# optocoupler_3.net
KiCad netlist of a schematic drawn in EAGLE
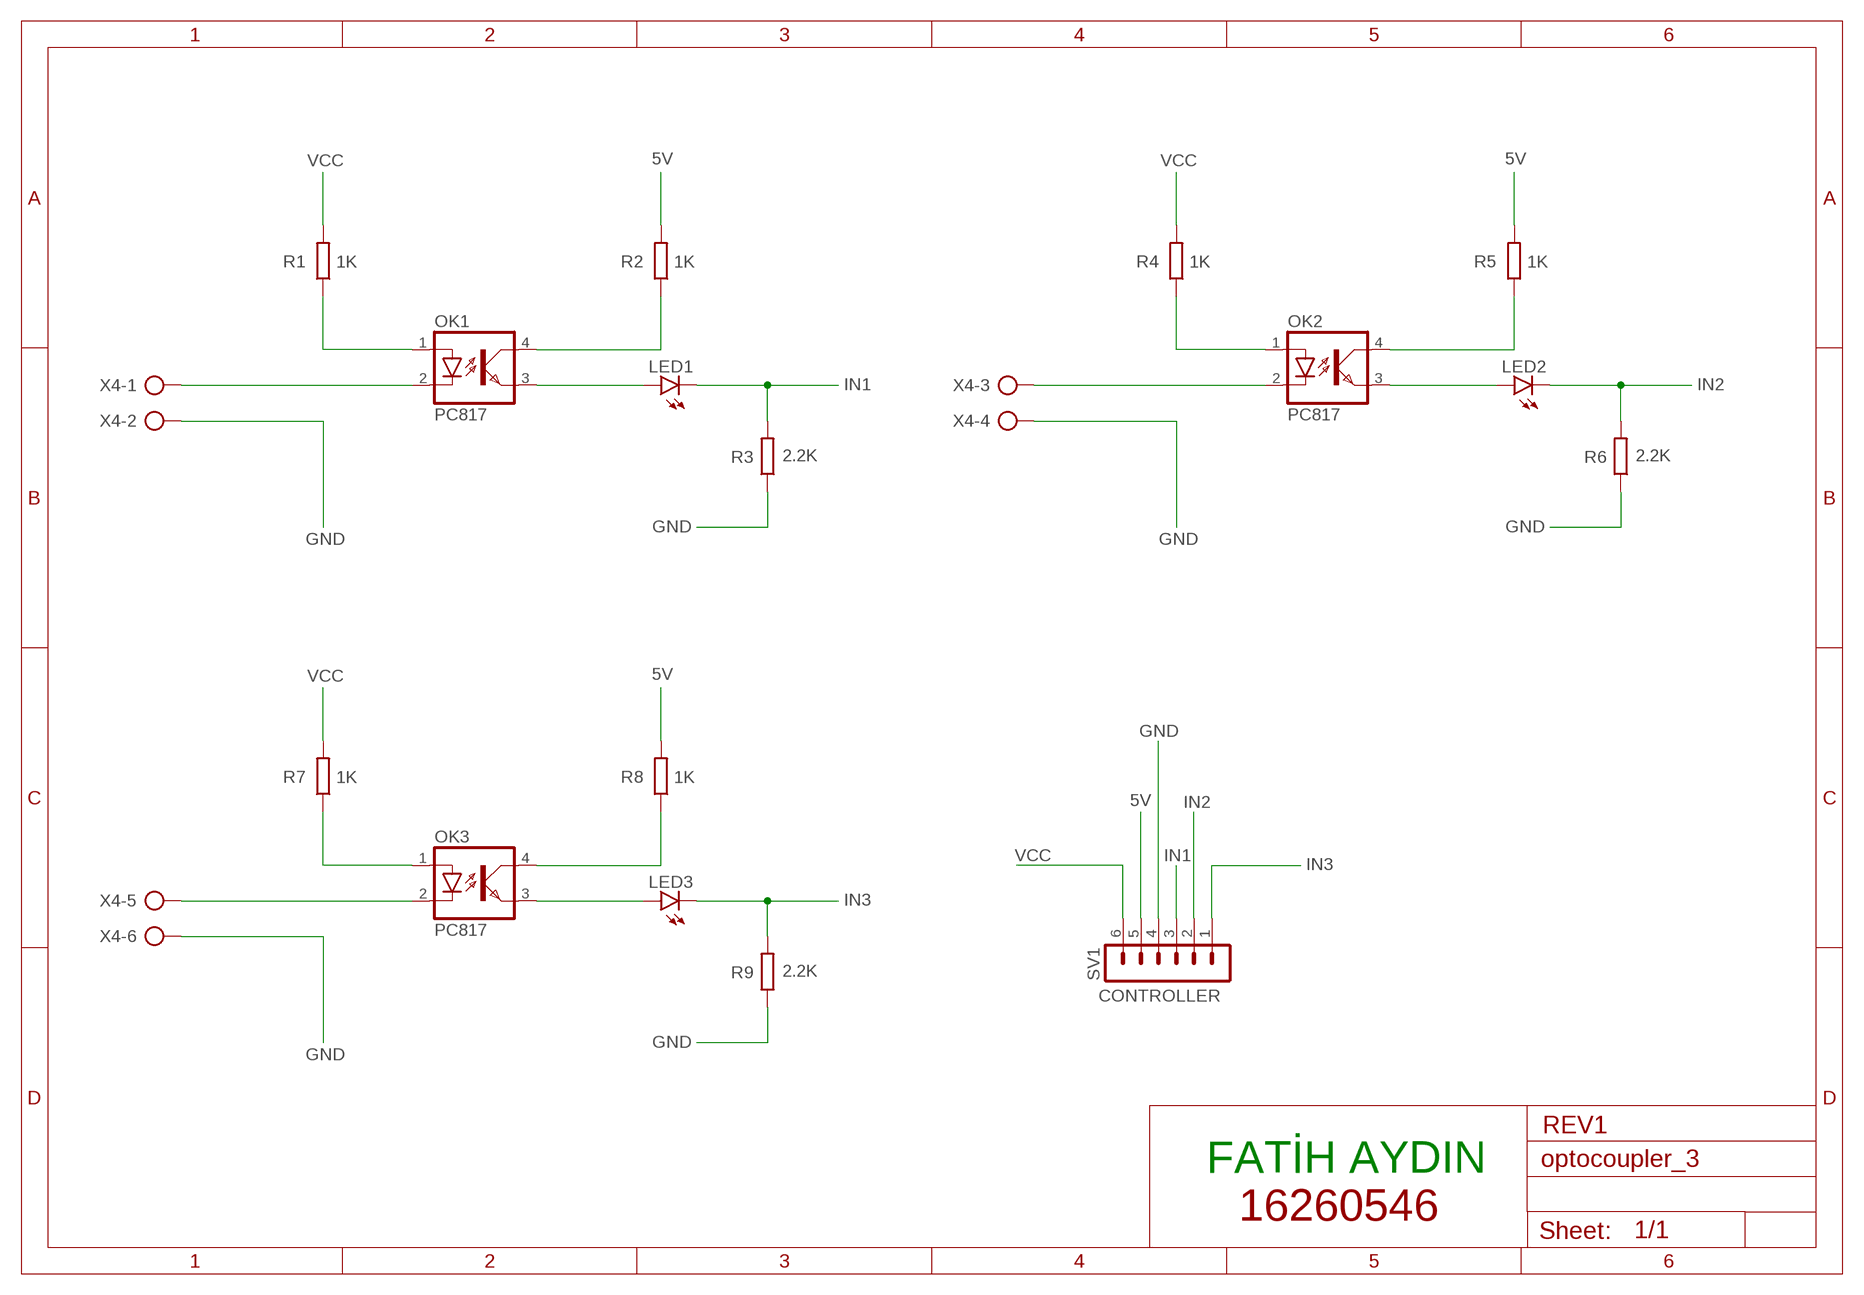
[diagram p0: schematic, sheet 1]

(export (version "E")
  (design (tool "Eeschema 10.0.6"))
  (components
    (comp (ref "LED1")
      (value "LED5MM")
      (footprint "eagle-import:LED5MM")
      (libsource (lib "eagle-import") (part "LED5MM"))
    )
    (comp (ref "LED2")
      (value "LED5MM")
      (footprint "eagle-import:LED5MM")
      (libsource (lib "eagle-import") (part "LED5MM"))
    )
    (comp (ref "LED3")
      (value "LED5MM")
      (footprint "eagle-import:LED5MM")
      (libsource (lib "eagle-import") (part "LED5MM"))
    )
    (comp (ref "OK1")
      (value "PC817")
      (footprint "eagle-import:DIL04")
      (fields (field (name "MPN") "PC817X4J000F"))
      (libsource (lib "eagle-import") (part "PC817"))
    )
    (comp (ref "OK2")
      (value "PC817")
      (footprint "eagle-import:DIL04")
      (fields (field (name "MPN") "PC817X4J000F"))
      (libsource (lib "eagle-import") (part "PC817"))
    )
    (comp (ref "OK3")
      (value "PC817")
      (footprint "eagle-import:DIL04")
      (fields (field (name "MPN") "PC817X4J000F"))
      (libsource (lib "eagle-import") (part "PC817"))
    )
    (comp (ref "R1")
      (value "1K")
      (footprint "eagle-import:0204_7")
      (libsource (lib "eagle-import") (part "R-EU_0204/7"))
    )
    (comp (ref "R2")
      (value "1K")
      (footprint "eagle-import:0204_7")
      (libsource (lib "eagle-import") (part "R-EU_0204/7"))
    )
    (comp (ref "R3")
      (value "2.2K")
      (footprint "eagle-import:0204_7")
      (libsource (lib "eagle-import") (part "R-EU_0204/7"))
    )
    (comp (ref "R4")
      (value "1K")
      (footprint "eagle-import:0204_7")
      (libsource (lib "eagle-import") (part "R-EU_0204/7"))
    )
    (comp (ref "R5")
      (value "1K")
      (footprint "eagle-import:0204_7")
      (libsource (lib "eagle-import") (part "R-EU_0204/7"))
    )
    (comp (ref "R6")
      (value "2.2K")
      (footprint "eagle-import:0204_7")
      (libsource (lib "eagle-import") (part "R-EU_0204/7"))
    )
    (comp (ref "R7")
      (value "1K")
      (footprint "eagle-import:0204_7")
      (libsource (lib "eagle-import") (part "R-EU_0204/7"))
    )
    (comp (ref "R8")
      (value "1K")
      (footprint "eagle-import:0204_7")
      (libsource (lib "eagle-import") (part "R-EU_0204/7"))
    )
    (comp (ref "R9")
      (value "2.2K")
      (footprint "eagle-import:0204_7")
      (libsource (lib "eagle-import") (part "R-EU_0204/7"))
    )
    (comp (ref "SV1")
      (value "CONTROLLER")
      (footprint "eagle-import:MA06-1")
      (libsource (lib "eagle-import") (part "MA06-1"))
    )
    (comp (ref "X4")
      (value "AK300/6")
      (footprint "eagle-import:AK300_6")
      (libsource (lib "eagle-import") (part "AK300/6"))
    )
  )
  (nets
    (net (code "1") (name "/5V") (class "Default")
      (node (ref "R2") (pin "2") (pinfunction "2_2") (pintype "passive"))
      (node (ref "R5") (pin "2") (pinfunction "2_2") (pintype "passive"))
      (node (ref "R8") (pin "2") (pinfunction "2_2") (pintype "passive"))
      (node (ref "SV1") (pin "5") (pinfunction "5_5") (pintype "passive"))
    )
    (net (code "2") (name "/GND") (class "Default")
      (node (ref "R3") (pin "1") (pinfunction "1_1") (pintype "passive"))
      (node (ref "R6") (pin "1") (pinfunction "1_1") (pintype "passive"))
      (node (ref "R9") (pin "1") (pinfunction "1_1") (pintype "passive"))
      (node (ref "SV1") (pin "4") (pinfunction "4_4") (pintype "passive"))
      (node (ref "X4") (pin "2") (pinfunction "KL_2") (pintype "passive"))
      (node (ref "X4") (pin "4") (pinfunction "KL_4") (pintype "passive"))
      (node (ref "X4") (pin "6") (pinfunction "KL_6") (pintype "passive"))
    )
    (net (code "3") (name "/IN1") (class "Default")
      (node (ref "LED1") (pin "K") (pinfunction "C_K") (pintype "passive"))
      (node (ref "R3") (pin "2") (pinfunction "2_2") (pintype "passive"))
      (node (ref "SV1") (pin "3") (pinfunction "3_3") (pintype "passive"))
    )
    (net (code "4") (name "/IN2") (class "Default")
      (node (ref "LED2") (pin "K") (pinfunction "C_K") (pintype "passive"))
      (node (ref "R6") (pin "2") (pinfunction "2_2") (pintype "passive"))
      (node (ref "SV1") (pin "2") (pinfunction "2_2") (pintype "passive"))
    )
    (net (code "5") (name "/IN3") (class "Default")
      (node (ref "LED3") (pin "K") (pinfunction "C_K") (pintype "passive"))
      (node (ref "R9") (pin "2") (pinfunction "2_2") (pintype "passive"))
      (node (ref "SV1") (pin "1") (pinfunction "1_1") (pintype "passive"))
    )
    (net (code "6") (name "/VCC") (class "Default")
      (node (ref "R1") (pin "2") (pinfunction "2_2") (pintype "passive"))
      (node (ref "R4") (pin "2") (pinfunction "2_2") (pintype "passive"))
      (node (ref "R7") (pin "2") (pinfunction "2_2") (pintype "passive"))
      (node (ref "SV1") (pin "6") (pinfunction "6_6") (pintype "passive"))
    )
    (net (code "7") (name "Net-(OK1-A)") (class "Default")
      (node (ref "OK1") (pin "1") (pinfunction "A_1") (pintype "passive"))
      (node (ref "R1") (pin "1") (pinfunction "1_1") (pintype "passive"))
    )
    (net (code "8") (name "Net-(OK1-C)") (class "Default")
      (node (ref "OK1") (pin "2") (pinfunction "C_2") (pintype "passive"))
      (node (ref "X4") (pin "1") (pinfunction "KL_1") (pintype "passive"))
    )
    (net (code "9") (name "Net-(OK1-COL)") (class "Default")
      (node (ref "OK1") (pin "4") (pinfunction "COL_4") (pintype "passive"))
      (node (ref "R2") (pin "1") (pinfunction "1_1") (pintype "passive"))
    )
    (net (code "10") (name "Net-(OK1-EMIT)") (class "Default")
      (node (ref "LED1") (pin "A") (pinfunction "A_A") (pintype "passive"))
      (node (ref "OK1") (pin "3") (pinfunction "EMIT_3") (pintype "passive"))
    )
    (net (code "11") (name "Net-(OK2-A)") (class "Default")
      (node (ref "OK2") (pin "1") (pinfunction "A_1") (pintype "passive"))
      (node (ref "R4") (pin "1") (pinfunction "1_1") (pintype "passive"))
    )
    (net (code "12") (name "Net-(OK2-C)") (class "Default")
      (node (ref "OK2") (pin "2") (pinfunction "C_2") (pintype "passive"))
      (node (ref "X4") (pin "3") (pinfunction "KL_3") (pintype "passive"))
    )
    (net (code "13") (name "Net-(OK2-COL)") (class "Default")
      (node (ref "OK2") (pin "4") (pinfunction "COL_4") (pintype "passive"))
      (node (ref "R5") (pin "1") (pinfunction "1_1") (pintype "passive"))
    )
    (net (code "14") (name "Net-(OK2-EMIT)") (class "Default")
      (node (ref "LED2") (pin "A") (pinfunction "A_A") (pintype "passive"))
      (node (ref "OK2") (pin "3") (pinfunction "EMIT_3") (pintype "passive"))
    )
    (net (code "15") (name "Net-(OK3-A)") (class "Default")
      (node (ref "OK3") (pin "1") (pinfunction "A_1") (pintype "passive"))
      (node (ref "R7") (pin "1") (pinfunction "1_1") (pintype "passive"))
    )
    (net (code "16") (name "Net-(OK3-C)") (class "Default")
      (node (ref "OK3") (pin "2") (pinfunction "C_2") (pintype "passive"))
      (node (ref "X4") (pin "5") (pinfunction "KL_5") (pintype "passive"))
    )
    (net (code "17") (name "Net-(OK3-COL)") (class "Default")
      (node (ref "OK3") (pin "4") (pinfunction "COL_4") (pintype "passive"))
      (node (ref "R8") (pin "1") (pinfunction "1_1") (pintype "passive"))
    )
    (net (code "18") (name "Net-(OK3-EMIT)") (class "Default")
      (node (ref "LED3") (pin "A") (pinfunction "A_A") (pintype "passive"))
      (node (ref "OK3") (pin "3") (pinfunction "EMIT_3") (pintype "passive"))
    )
  )
)
